# MSSRP-PRESSURE_GEN_AFE.net
KiCad netlist of a schematic drawn in EAGLE
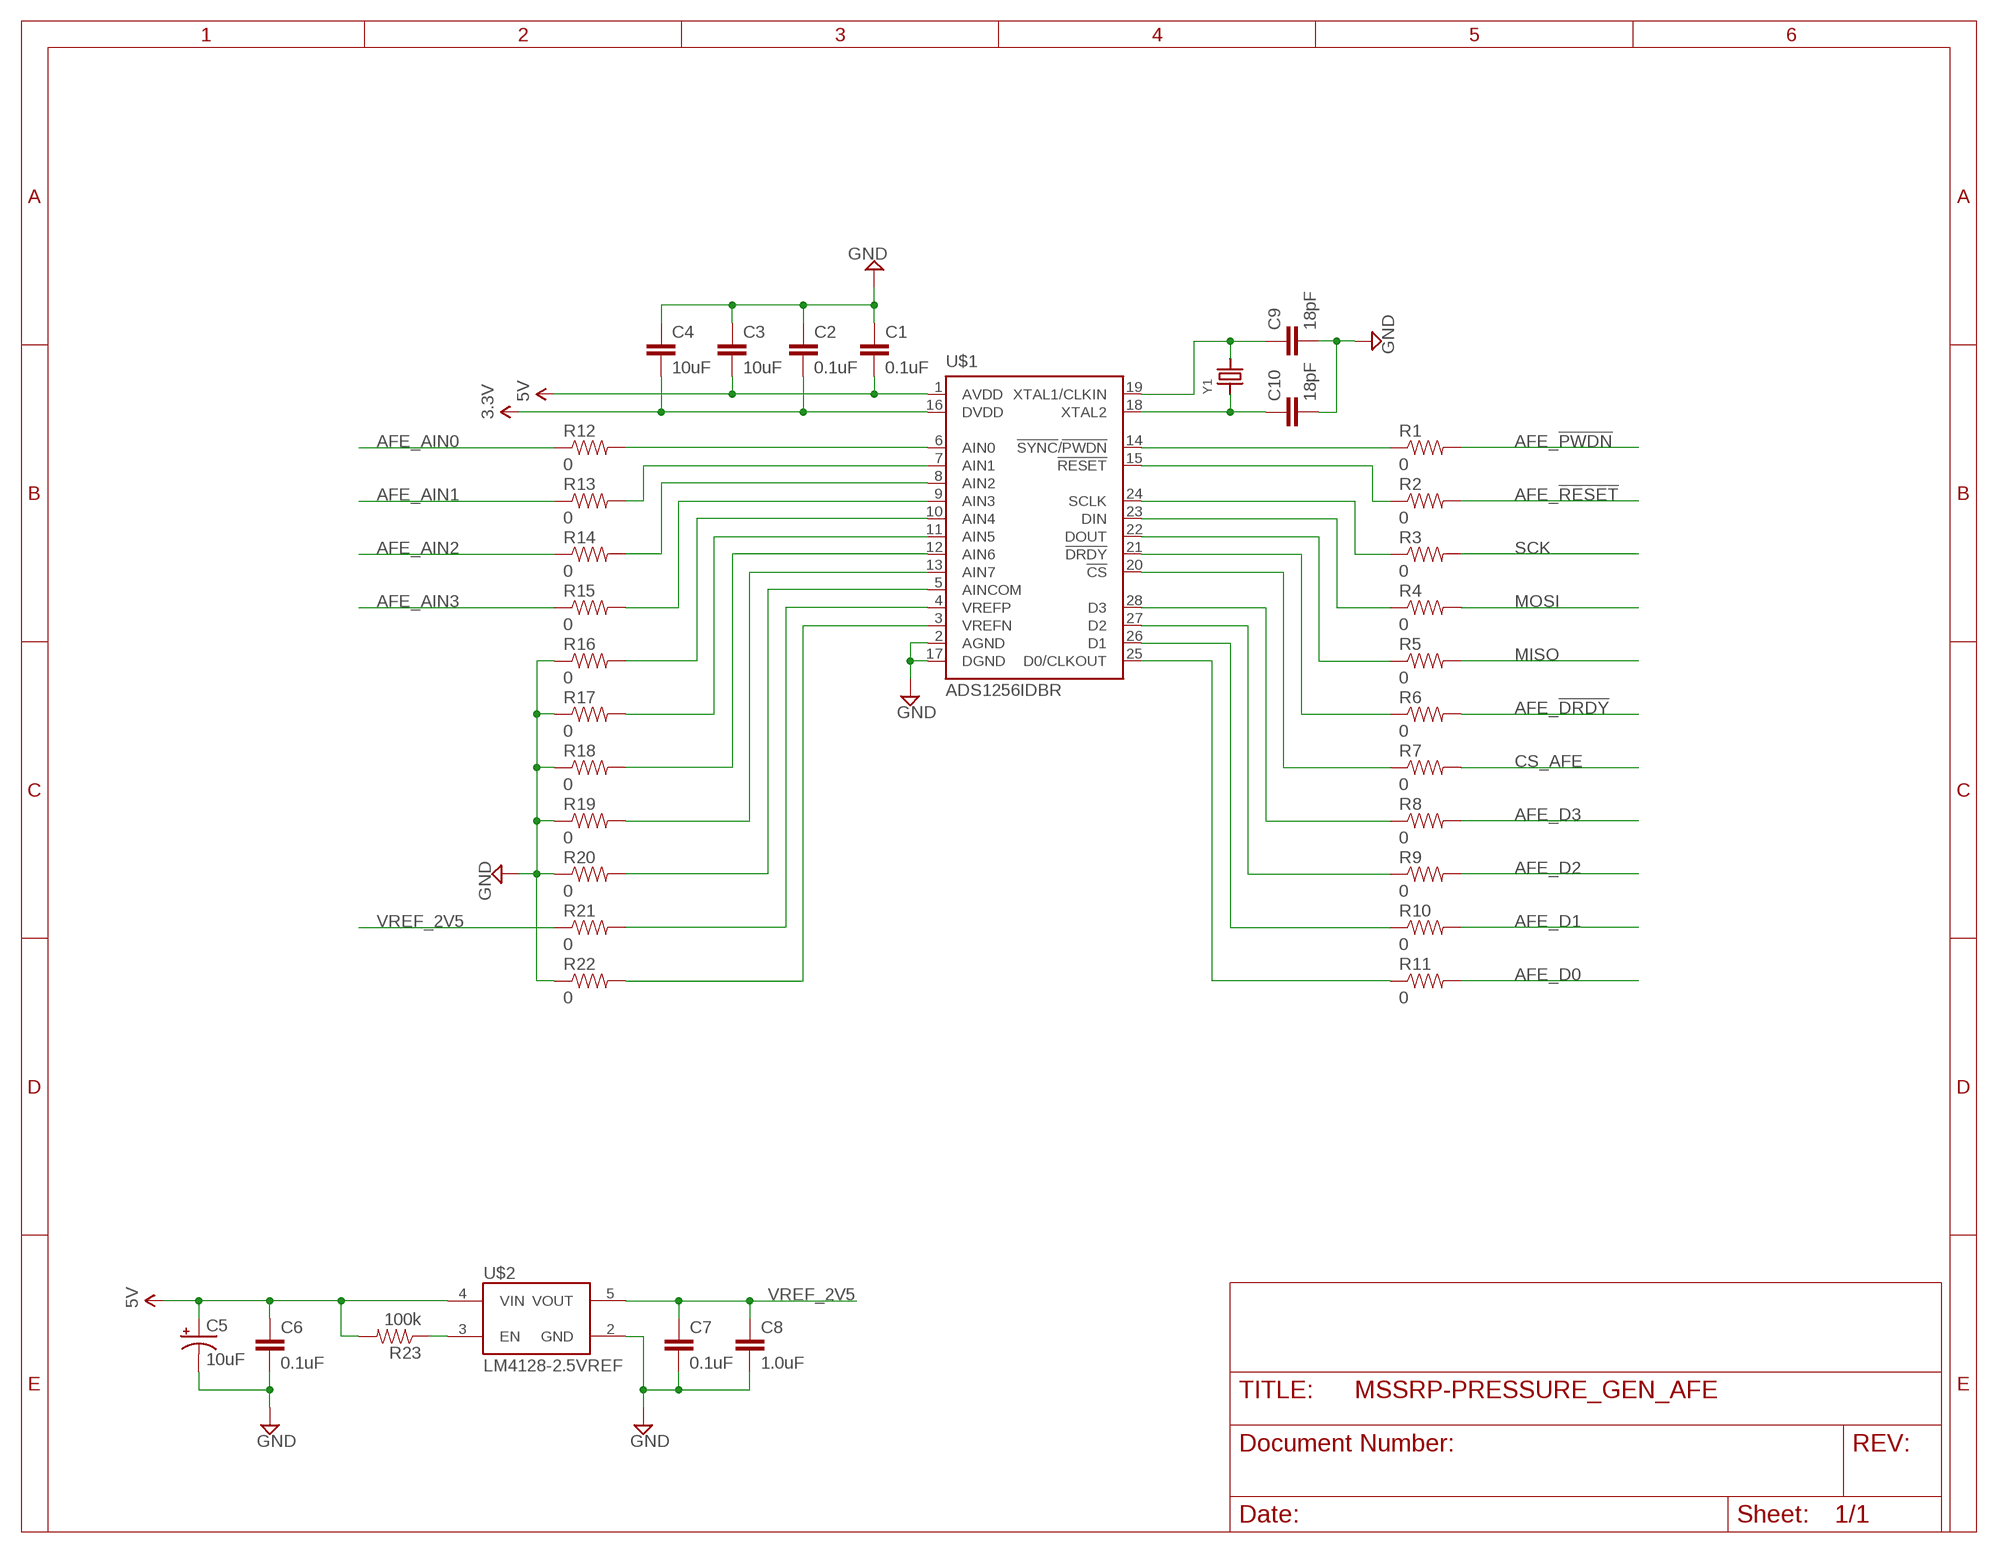
[diagram p0: schematic, sheet 1]

(export (version "E")
  (design (tool "Eeschema 10.0.6"))
  (components
    (comp (ref "C1")
      (value "0.1uF")
      (footprint "eagle-import:0603-CAP")
      (libsource (lib "eagle-import") (part "0.1UF-25V-5%(0603)"))
    )
    (comp (ref "C2")
      (value "0.1uF")
      (footprint "eagle-import:0603-CAP")
      (libsource (lib "eagle-import") (part "0.1UF-25V-5%(0603)"))
    )
    (comp (ref "C3")
      (value "10uF")
      (footprint "eagle-import:0603-CAP")
      (libsource (lib "eagle-import") (part "10UF-6.3V-20%(0603)"))
    )
    (comp (ref "C4")
      (value "10uF")
      (footprint "eagle-import:0603-CAP")
      (libsource (lib "eagle-import") (part "10UF-6.3V-20%(0603)"))
    )
    (comp (ref "C5")
      (value "10uF")
      (footprint "eagle-import:EIA3216")
      (libsource (lib "eagle-import") (part "10UF-16V-10%(TANT)"))
    )
    (comp (ref "C6")
      (value "0.1uF")
      (footprint "eagle-import:0603-CAP")
      (libsource (lib "eagle-import") (part "0.1UF-25V-5%(0603)"))
    )
    (comp (ref "C7")
      (value "0.1uF")
      (footprint "eagle-import:0603-CAP")
      (libsource (lib "eagle-import") (part "0.1UF-25V-5%(0603)"))
    )
    (comp (ref "C8")
      (value "1.0uF")
      (footprint "eagle-import:0603-CAP")
      (libsource (lib "eagle-import") (part "1.0UF-16V-10%(0603)"))
    )
    (comp (ref "C9")
      (value "18pF")
      (footprint "eagle-import:0603-CAP")
      (libsource (lib "eagle-import") (part "18PF-50V-5%(0603)"))
    )
    (comp (ref "C10")
      (value "18pF")
      (footprint "eagle-import:0603-CAP")
      (libsource (lib "eagle-import") (part "18PF-50V-5%(0603)"))
    )
    (comp (ref "R1")
      (value "0")
      (footprint "eagle-import:0603")
      (libsource (lib "eagle-import") (part "0OHM1/10W5%(0603)"))
    )
    (comp (ref "R2")
      (value "0")
      (footprint "eagle-import:0603")
      (libsource (lib "eagle-import") (part "0OHM1/10W5%(0603)"))
    )
    (comp (ref "R3")
      (value "0")
      (footprint "eagle-import:0603")
      (libsource (lib "eagle-import") (part "0OHM1/10W5%(0603)"))
    )
    (comp (ref "R4")
      (value "0")
      (footprint "eagle-import:0603")
      (libsource (lib "eagle-import") (part "0OHM1/10W5%(0603)"))
    )
    (comp (ref "R5")
      (value "0")
      (footprint "eagle-import:0603")
      (libsource (lib "eagle-import") (part "0OHM1/10W5%(0603)"))
    )
    (comp (ref "R6")
      (value "0")
      (footprint "eagle-import:0603")
      (libsource (lib "eagle-import") (part "0OHM1/10W5%(0603)"))
    )
    (comp (ref "R7")
      (value "0")
      (footprint "eagle-import:0603")
      (libsource (lib "eagle-import") (part "0OHM1/10W5%(0603)"))
    )
    (comp (ref "R8")
      (value "0")
      (footprint "eagle-import:0603")
      (libsource (lib "eagle-import") (part "0OHM1/10W5%(0603)"))
    )
    (comp (ref "R9")
      (value "0")
      (footprint "eagle-import:0603")
      (libsource (lib "eagle-import") (part "0OHM1/10W5%(0603)"))
    )
    (comp (ref "R10")
      (value "0")
      (footprint "eagle-import:0603")
      (libsource (lib "eagle-import") (part "0OHM1/10W5%(0603)"))
    )
    (comp (ref "R11")
      (value "0")
      (footprint "eagle-import:0603")
      (libsource (lib "eagle-import") (part "0OHM1/10W5%(0603)"))
    )
    (comp (ref "R12")
      (value "0")
      (footprint "eagle-import:0603")
      (libsource (lib "eagle-import") (part "0OHM1/10W5%(0603)"))
    )
    (comp (ref "R13")
      (value "0")
      (footprint "eagle-import:0603")
      (libsource (lib "eagle-import") (part "0OHM1/10W5%(0603)"))
    )
    (comp (ref "R14")
      (value "0")
      (footprint "eagle-import:0603")
      (libsource (lib "eagle-import") (part "0OHM1/10W5%(0603)"))
    )
    (comp (ref "R15")
      (value "0")
      (footprint "eagle-import:0603")
      (libsource (lib "eagle-import") (part "0OHM1/10W5%(0603)"))
    )
    (comp (ref "R16")
      (value "0")
      (footprint "eagle-import:0603")
      (libsource (lib "eagle-import") (part "0OHM1/10W5%(0603)"))
    )
    (comp (ref "R17")
      (value "0")
      (footprint "eagle-import:0603")
      (libsource (lib "eagle-import") (part "0OHM1/10W5%(0603)"))
    )
    (comp (ref "R18")
      (value "0")
      (footprint "eagle-import:0603")
      (libsource (lib "eagle-import") (part "0OHM1/10W5%(0603)"))
    )
    (comp (ref "R19")
      (value "0")
      (footprint "eagle-import:0603")
      (libsource (lib "eagle-import") (part "0OHM1/10W5%(0603)"))
    )
    (comp (ref "R20")
      (value "0")
      (footprint "eagle-import:0603")
      (libsource (lib "eagle-import") (part "0OHM1/10W5%(0603)"))
    )
    (comp (ref "R21")
      (value "0")
      (footprint "eagle-import:0603")
      (libsource (lib "eagle-import") (part "0OHM1/10W5%(0603)"))
    )
    (comp (ref "R22")
      (value "0")
      (footprint "eagle-import:0603")
      (libsource (lib "eagle-import") (part "0OHM1/10W5%(0603)"))
    )
    (comp (ref "R23")
      (value "100k")
      (footprint "eagle-import:0603-RES")
      (libsource (lib "eagle-import") (part "100KOHM1/10W1%(0603)"))
    )
    (comp (ref "U$1")
      (value "ADS1256IDBR")
      (footprint "eagle-import:SSOP28")
      (libsource (lib "eagle-import") (part "ADS1256IDBR"))
    )
    (comp (ref "U$2")
      (value "LM4128-2.5VREF")
      (footprint "eagle-import:SOT23-5")
      (libsource (lib "eagle-import") (part "LM4128-2.5VREF"))
    )
    (comp (ref "Y1")
      (value "CRYSTALSMD")
      (footprint "eagle-import:HC49UP")
      (libsource (lib "eagle-import") (part "CRYSTALSMD"))
    )
  )
  (nets
    (net (code "1") (name "/AFE_AIN0") (class "Default")
      (node (ref "R12") (pin "1") (pinfunction "1_1") (pintype "passive"))
    )
    (net (code "2") (name "/AFE_AIN1") (class "Default")
      (node (ref "R13") (pin "1") (pinfunction "1_1") (pintype "passive"))
    )
    (net (code "3") (name "/AFE_AIN2") (class "Default")
      (node (ref "R14") (pin "1") (pinfunction "1_1") (pintype "passive"))
    )
    (net (code "4") (name "/AFE_AIN3") (class "Default")
      (node (ref "R15") (pin "1") (pinfunction "1_1") (pintype "passive"))
    )
    (net (code "5") (name "/AFE_D0") (class "Default")
      (node (ref "R11") (pin "2") (pinfunction "2_2") (pintype "passive"))
    )
    (net (code "6") (name "/AFE_D1") (class "Default")
      (node (ref "R10") (pin "2") (pinfunction "2_2") (pintype "passive"))
    )
    (net (code "7") (name "/AFE_D2") (class "Default")
      (node (ref "R9") (pin "2") (pinfunction "2_2") (pintype "passive"))
    )
    (net (code "8") (name "/AFE_D3") (class "Default")
      (node (ref "R8") (pin "2") (pinfunction "2_2") (pintype "passive"))
    )
    (net (code "9") (name "/AFE_~{DRDY}") (class "Default")
      (node (ref "R6") (pin "2") (pinfunction "2_2") (pintype "passive"))
    )
    (net (code "10") (name "/AFE_~{PWDN}") (class "Default")
      (node (ref "R1") (pin "2") (pinfunction "2_2") (pintype "passive"))
    )
    (net (code "11") (name "/AFE_~{RESET}") (class "Default")
      (node (ref "R2") (pin "2") (pinfunction "2_2") (pintype "passive"))
    )
    (net (code "12") (name "/CS_AFE") (class "Default")
      (node (ref "R7") (pin "2") (pinfunction "2_2") (pintype "passive"))
    )
    (net (code "13") (name "/MISO") (class "Default")
      (node (ref "R5") (pin "2") (pinfunction "2_2") (pintype "passive"))
    )
    (net (code "14") (name "/MOSI") (class "Default")
      (node (ref "R4") (pin "2") (pinfunction "2_2") (pintype "passive"))
    )
    (net (code "15") (name "/SCK") (class "Default")
      (node (ref "R3") (pin "2") (pinfunction "2_2") (pintype "passive"))
    )
    (net (code "16") (name "/VREF_2V5") (class "Default")
      (node (ref "C7") (pin "1") (pinfunction "1_1") (pintype "passive"))
      (node (ref "C8") (pin "1") (pinfunction "1_1") (pintype "passive"))
      (node (ref "R21") (pin "1") (pinfunction "1_1") (pintype "passive"))
      (node (ref "U$2") (pin "5") (pinfunction "VOUT_5") (pintype "bidirectional"))
    )
    (net (code "17") (name "3.3V") (class "Default")
      (node (ref "C2") (pin "2") (pinfunction "2_2") (pintype "passive"))
      (node (ref "C4") (pin "2") (pinfunction "2_2") (pintype "passive"))
      (node (ref "U$1") (pin "16") (pinfunction "DVDD_16") (pintype "power_in"))
    )
    (net (code "18") (name "5V") (class "Default")
      (node (ref "C1") (pin "2") (pinfunction "2_2") (pintype "passive"))
      (node (ref "C3") (pin "2") (pinfunction "2_2") (pintype "passive"))
      (node (ref "C5") (pin "A") (pinfunction "+_A") (pintype "passive"))
      (node (ref "C6") (pin "1") (pinfunction "1_1") (pintype "passive"))
      (node (ref "R23") (pin "2") (pinfunction "2_2") (pintype "passive"))
      (node (ref "U$1") (pin "1") (pinfunction "AVDD_1") (pintype "power_in"))
      (node (ref "U$2") (pin "4") (pinfunction "VIN_4") (pintype "bidirectional"))
    )
    (net (code "19") (name "GND") (class "Default")
      (node (ref "C1") (pin "1") (pinfunction "1_1") (pintype "passive"))
      (node (ref "C10") (pin "2") (pinfunction "2_2") (pintype "passive"))
      (node (ref "C2") (pin "1") (pinfunction "1_1") (pintype "passive"))
      (node (ref "C3") (pin "1") (pinfunction "1_1") (pintype "passive"))
      (node (ref "C4") (pin "1") (pinfunction "1_1") (pintype "passive"))
      (node (ref "C5") (pin "C") (pinfunction "-_C") (pintype "passive"))
      (node (ref "C6") (pin "2") (pinfunction "2_2") (pintype "passive"))
      (node (ref "C7") (pin "2") (pinfunction "2_2") (pintype "passive"))
      (node (ref "C8") (pin "2") (pinfunction "2_2") (pintype "passive"))
      (node (ref "C9") (pin "2") (pinfunction "2_2") (pintype "passive"))
      (node (ref "R16") (pin "1") (pinfunction "1_1") (pintype "passive"))
      (node (ref "R17") (pin "1") (pinfunction "1_1") (pintype "passive"))
      (node (ref "R18") (pin "1") (pinfunction "1_1") (pintype "passive"))
      (node (ref "R19") (pin "1") (pinfunction "1_1") (pintype "passive"))
      (node (ref "R20") (pin "1") (pinfunction "1_1") (pintype "passive"))
      (node (ref "R22") (pin "1") (pinfunction "1_1") (pintype "passive"))
      (node (ref "U$1") (pin "17") (pinfunction "DGND_17") (pintype "power_in"))
      (node (ref "U$1") (pin "2") (pinfunction "AGND_2") (pintype "power_in"))
      (node (ref "U$2") (pin "2") (pinfunction "GND_2") (pintype "bidirectional"))
    )
    (net (code "20") (name "Net-(U$1-AIN0)") (class "Default")
      (node (ref "R12") (pin "2") (pinfunction "2_2") (pintype "passive"))
      (node (ref "U$1") (pin "6") (pinfunction "AIN0_6") (pintype "input"))
    )
    (net (code "21") (name "Net-(U$1-AIN1)") (class "Default")
      (node (ref "R13") (pin "2") (pinfunction "2_2") (pintype "passive"))
      (node (ref "U$1") (pin "7") (pinfunction "AIN1_7") (pintype "input"))
    )
    (net (code "22") (name "Net-(U$1-AIN2)") (class "Default")
      (node (ref "R14") (pin "2") (pinfunction "2_2") (pintype "passive"))
      (node (ref "U$1") (pin "8") (pinfunction "AIN2_8") (pintype "input"))
    )
    (net (code "23") (name "Net-(U$1-AIN3)") (class "Default")
      (node (ref "R15") (pin "2") (pinfunction "2_2") (pintype "passive"))
      (node (ref "U$1") (pin "9") (pinfunction "AIN3_9") (pintype "input"))
    )
    (net (code "24") (name "Net-(U$1-AIN4)") (class "Default")
      (node (ref "R16") (pin "2") (pinfunction "2_2") (pintype "passive"))
      (node (ref "U$1") (pin "10") (pinfunction "AIN4_10") (pintype "input"))
    )
    (net (code "25") (name "Net-(U$1-AIN5)") (class "Default")
      (node (ref "R17") (pin "2") (pinfunction "2_2") (pintype "passive"))
      (node (ref "U$1") (pin "11") (pinfunction "AIN5_11") (pintype "input"))
    )
    (net (code "26") (name "Net-(U$1-AIN6)") (class "Default")
      (node (ref "R18") (pin "2") (pinfunction "2_2") (pintype "passive"))
      (node (ref "U$1") (pin "12") (pinfunction "AIN6_12") (pintype "input"))
    )
    (net (code "27") (name "Net-(U$1-AIN7)") (class "Default")
      (node (ref "R19") (pin "2") (pinfunction "2_2") (pintype "passive"))
      (node (ref "U$1") (pin "13") (pinfunction "AIN7_13") (pintype "input"))
    )
    (net (code "28") (name "Net-(U$1-AINCOM)") (class "Default")
      (node (ref "R20") (pin "2") (pinfunction "2_2") (pintype "passive"))
      (node (ref "U$1") (pin "5") (pinfunction "AINCOM_5") (pintype "input"))
    )
    (net (code "29") (name "Net-(U$1-D0{slash}CLKOUT)") (class "Default")
      (node (ref "R11") (pin "1") (pinfunction "1_1") (pintype "passive"))
      (node (ref "U$1") (pin "25") (pinfunction "D0/CLKOUT_25") (pintype "bidirectional"))
    )
    (net (code "30") (name "Net-(U$1-D1)") (class "Default")
      (node (ref "R10") (pin "1") (pinfunction "1_1") (pintype "passive"))
      (node (ref "U$1") (pin "26") (pinfunction "D1_26") (pintype "bidirectional"))
    )
    (net (code "31") (name "Net-(U$1-D2)") (class "Default")
      (node (ref "R9") (pin "1") (pinfunction "1_1") (pintype "passive"))
      (node (ref "U$1") (pin "27") (pinfunction "D2_27") (pintype "bidirectional"))
    )
    (net (code "32") (name "Net-(U$1-D3)") (class "Default")
      (node (ref "R8") (pin "1") (pinfunction "1_1") (pintype "passive"))
      (node (ref "U$1") (pin "28") (pinfunction "D3_28") (pintype "bidirectional"))
    )
    (net (code "33") (name "Net-(U$1-DIN)") (class "Default")
      (node (ref "R4") (pin "1") (pinfunction "1_1") (pintype "passive"))
      (node (ref "U$1") (pin "23") (pinfunction "DIN_23") (pintype "bidirectional"))
    )
    (net (code "34") (name "Net-(U$1-DOUT)") (class "Default")
      (node (ref "R5") (pin "1") (pinfunction "1_1") (pintype "passive"))
      (node (ref "U$1") (pin "22") (pinfunction "DOUT_22") (pintype "output"))
    )
    (net (code "35") (name "Net-(U$1-SCLK)") (class "Default")
      (node (ref "R3") (pin "1") (pinfunction "1_1") (pintype "passive"))
      (node (ref "U$1") (pin "24") (pinfunction "SCLK_24") (pintype "bidirectional"))
    )
    (net (code "36") (name "Net-(U$1-VREFN)") (class "Default")
      (node (ref "R22") (pin "2") (pinfunction "2_2") (pintype "passive"))
      (node (ref "U$1") (pin "3") (pinfunction "VREFN_3") (pintype "passive"))
    )
    (net (code "37") (name "Net-(U$1-VREFP)") (class "Default")
      (node (ref "R21") (pin "2") (pinfunction "2_2") (pintype "passive"))
      (node (ref "U$1") (pin "4") (pinfunction "VREFP_4") (pintype "passive"))
    )
    (net (code "38") (name "Net-(U$1-XTAL1{slash}CLKIN)") (class "Default")
      (node (ref "C9") (pin "1") (pinfunction "1_1") (pintype "passive"))
      (node (ref "U$1") (pin "19") (pinfunction "XTAL1/CLKIN_19") (pintype "input"))
      (node (ref "Y1") (pin "2") (pinfunction "2_2") (pintype "passive"))
    )
    (net (code "39") (name "Net-(U$1-XTAL2)") (class "Default")
      (node (ref "C10") (pin "1") (pinfunction "1_1") (pintype "passive"))
      (node (ref "U$1") (pin "18") (pinfunction "XTAL2_18") (pintype "input"))
      (node (ref "Y1") (pin "1") (pinfunction "1_1") (pintype "passive"))
    )
    (net (code "40") (name "Net-(U$1-~{CS})") (class "Default")
      (node (ref "R7") (pin "1") (pinfunction "1_1") (pintype "passive"))
      (node (ref "U$1") (pin "20") (pinfunction "~{CS}_20") (pintype "input"))
    )
    (net (code "41") (name "Net-(U$1-~{DRDY})") (class "Default")
      (node (ref "R6") (pin "1") (pinfunction "1_1") (pintype "passive"))
      (node (ref "U$1") (pin "21") (pinfunction "~{DRDY}_21") (pintype "output"))
    )
    (net (code "42") (name "Net-(U$1-~{RESET})") (class "Default")
      (node (ref "R2") (pin "1") (pinfunction "1_1") (pintype "passive"))
      (node (ref "U$1") (pin "15") (pinfunction "~{RESET}_15") (pintype "input"))
    )
    (net (code "43") (name "Net-(U$1-~{SYNC}{slash}~{PWDN})") (class "Default")
      (node (ref "R1") (pin "1") (pinfunction "1_1") (pintype "passive"))
      (node (ref "U$1") (pin "14") (pinfunction "~{SYNC}/~{PWDN}_14") (pintype "input"))
    )
    (net (code "44") (name "Net-(U$2-EN)") (class "Default")
      (node (ref "R23") (pin "1") (pinfunction "1_1") (pintype "passive"))
      (node (ref "U$2") (pin "3") (pinfunction "EN_3") (pintype "bidirectional"))
    )
  )
)
